# IR.net
KiCad netlist of a schematic drawn in EAGLE
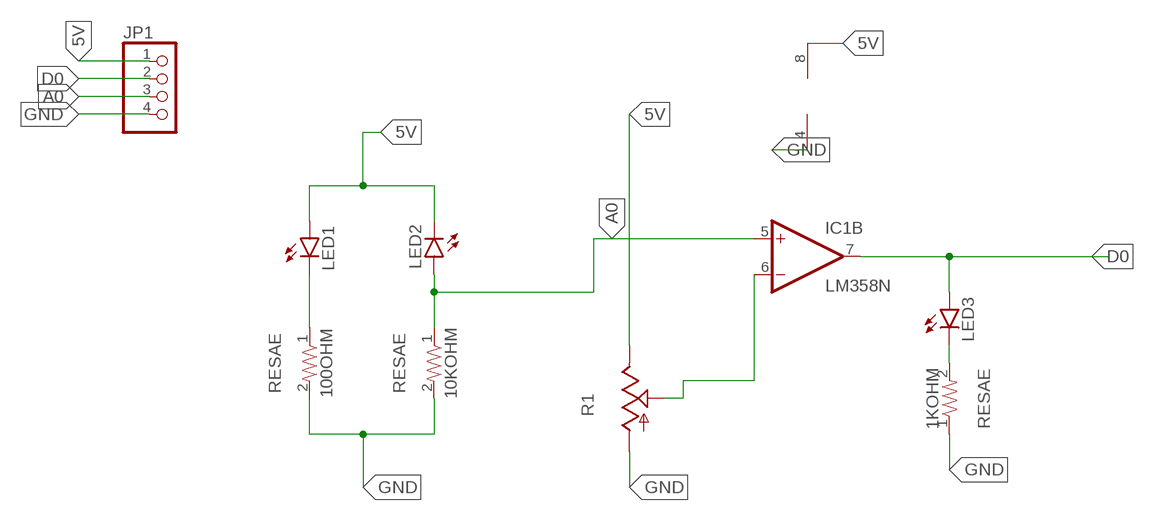
[diagram p0: schematic, sheet 1]

(export (version "E")
  (design (tool "Eeschema 10.0.6"))
  (components
    (comp (ref "1KOHM")
      (value "RESAE")
      (footprint "eagle-import:RESAD846W63L520D250B")
      (libsource (lib "eagle-import") (part "RESAE"))
    )
    (comp (ref "10KOHM")
      (value "RESAE")
      (footprint "eagle-import:RESAD846W63L520D250B")
      (libsource (lib "eagle-import") (part "RESAE"))
    )
    (comp (ref "100OHM")
      (value "RESAE")
      (footprint "eagle-import:RESAD846W63L520D250B")
      (libsource (lib "eagle-import") (part "RESAE"))
    )
    (comp (ref "IC1")
      (value "LM358N")
      (footprint "eagle-import:DIL08")
      (libsource (lib "eagle-import") (part "LM358N"))
    )
    (comp (ref "JP1")
      (value "PINHD-1X4/90")
      (footprint "eagle-import:1X04_90")
      (libsource (lib "eagle-import") (part "PINHD-1X4/90"))
    )
    (comp (ref "LED1")
      (value "LED5MM")
      (footprint "eagle-import:LED5MM")
      (libsource (lib "eagle-import") (part "LED5MM"))
    )
    (comp (ref "LED2")
      (value "LED5MM")
      (footprint "eagle-import:LED5MM")
      (libsource (lib "eagle-import") (part "LED5MM"))
    )
    (comp (ref "LED3")
      (value "LED3MM")
      (footprint "eagle-import:LED3MM")
      (libsource (lib "eagle-import") (part "LED3MM"))
    )
    (comp (ref "R1")
      (value "TRIM_US-CA6V")
      (footprint "eagle-import:CA6V")
      (libsource (lib "eagle-import") (part "TRIM_US-CA6V"))
    )
  )
  (nets
    (net (code "1") (name "5V") (class "Default")
      (node (ref "IC1") (pin "8") (pinfunction "V+_8") (pintype "power_in"))
      (node (ref "JP1") (pin "1") (pinfunction "1_1") (pintype "passive"))
      (node (ref "LED1") (pin "A") (pinfunction "A_A") (pintype "passive"))
      (node (ref "LED2") (pin "K") (pinfunction "C_K") (pintype "passive"))
      (node (ref "R1") (pin "E") (pinfunction "E_E") (pintype "passive"))
    )
    (net (code "2") (name "A0") (class "Default")
      (node (ref "10KOHM") (pin "1") (pinfunction "1_1") (pintype "passive"))
      (node (ref "IC1") (pin "5") (pinfunction "+IN_5") (pintype "input"))
      (node (ref "JP1") (pin "3") (pinfunction "3_3") (pintype "passive"))
      (node (ref "LED2") (pin "A") (pinfunction "A_A") (pintype "passive"))
    )
    (net (code "3") (name "D0") (class "Default")
      (node (ref "IC1") (pin "7") (pinfunction "OUT_7") (pintype "output"))
      (node (ref "JP1") (pin "2") (pinfunction "2_2") (pintype "passive"))
      (node (ref "LED3") (pin "A") (pinfunction "A_A") (pintype "passive"))
    )
    (net (code "4") (name "GND") (class "Default")
      (node (ref "100OHM") (pin "2") (pinfunction "2_2") (pintype "passive"))
      (node (ref "10KOHM") (pin "2") (pinfunction "2_2") (pintype "passive"))
      (node (ref "1KOHM") (pin "1") (pinfunction "1_1") (pintype "passive"))
      (node (ref "IC1") (pin "4") (pinfunction "V-_4") (pintype "power_in"))
      (node (ref "JP1") (pin "4") (pinfunction "4_4") (pintype "passive"))
      (node (ref "R1") (pin "A") (pinfunction "A_A") (pintype "passive"))
    )
    (net (code "5") (name "Net-(IC1B--IN)") (class "Default")
      (node (ref "IC1") (pin "6") (pinfunction "-IN_6") (pintype "input"))
      (node (ref "R1") (pin "S") (pinfunction "S_S") (pintype "passive"))
    )
    (net (code "6") (name "Net-(LED1-C)") (class "Default")
      (node (ref "100OHM") (pin "1") (pinfunction "1_1") (pintype "passive"))
      (node (ref "LED1") (pin "K") (pinfunction "C_K") (pintype "passive"))
    )
    (net (code "7") (name "Net-(LED3-C)") (class "Default")
      (node (ref "1KOHM") (pin "2") (pinfunction "2_2") (pintype "passive"))
      (node (ref "LED3") (pin "K") (pinfunction "C_K") (pintype "passive"))
    )
  )
)
